# NaNd_synth_v0_1.net
KiCad netlist of a schematic drawn in EAGLE
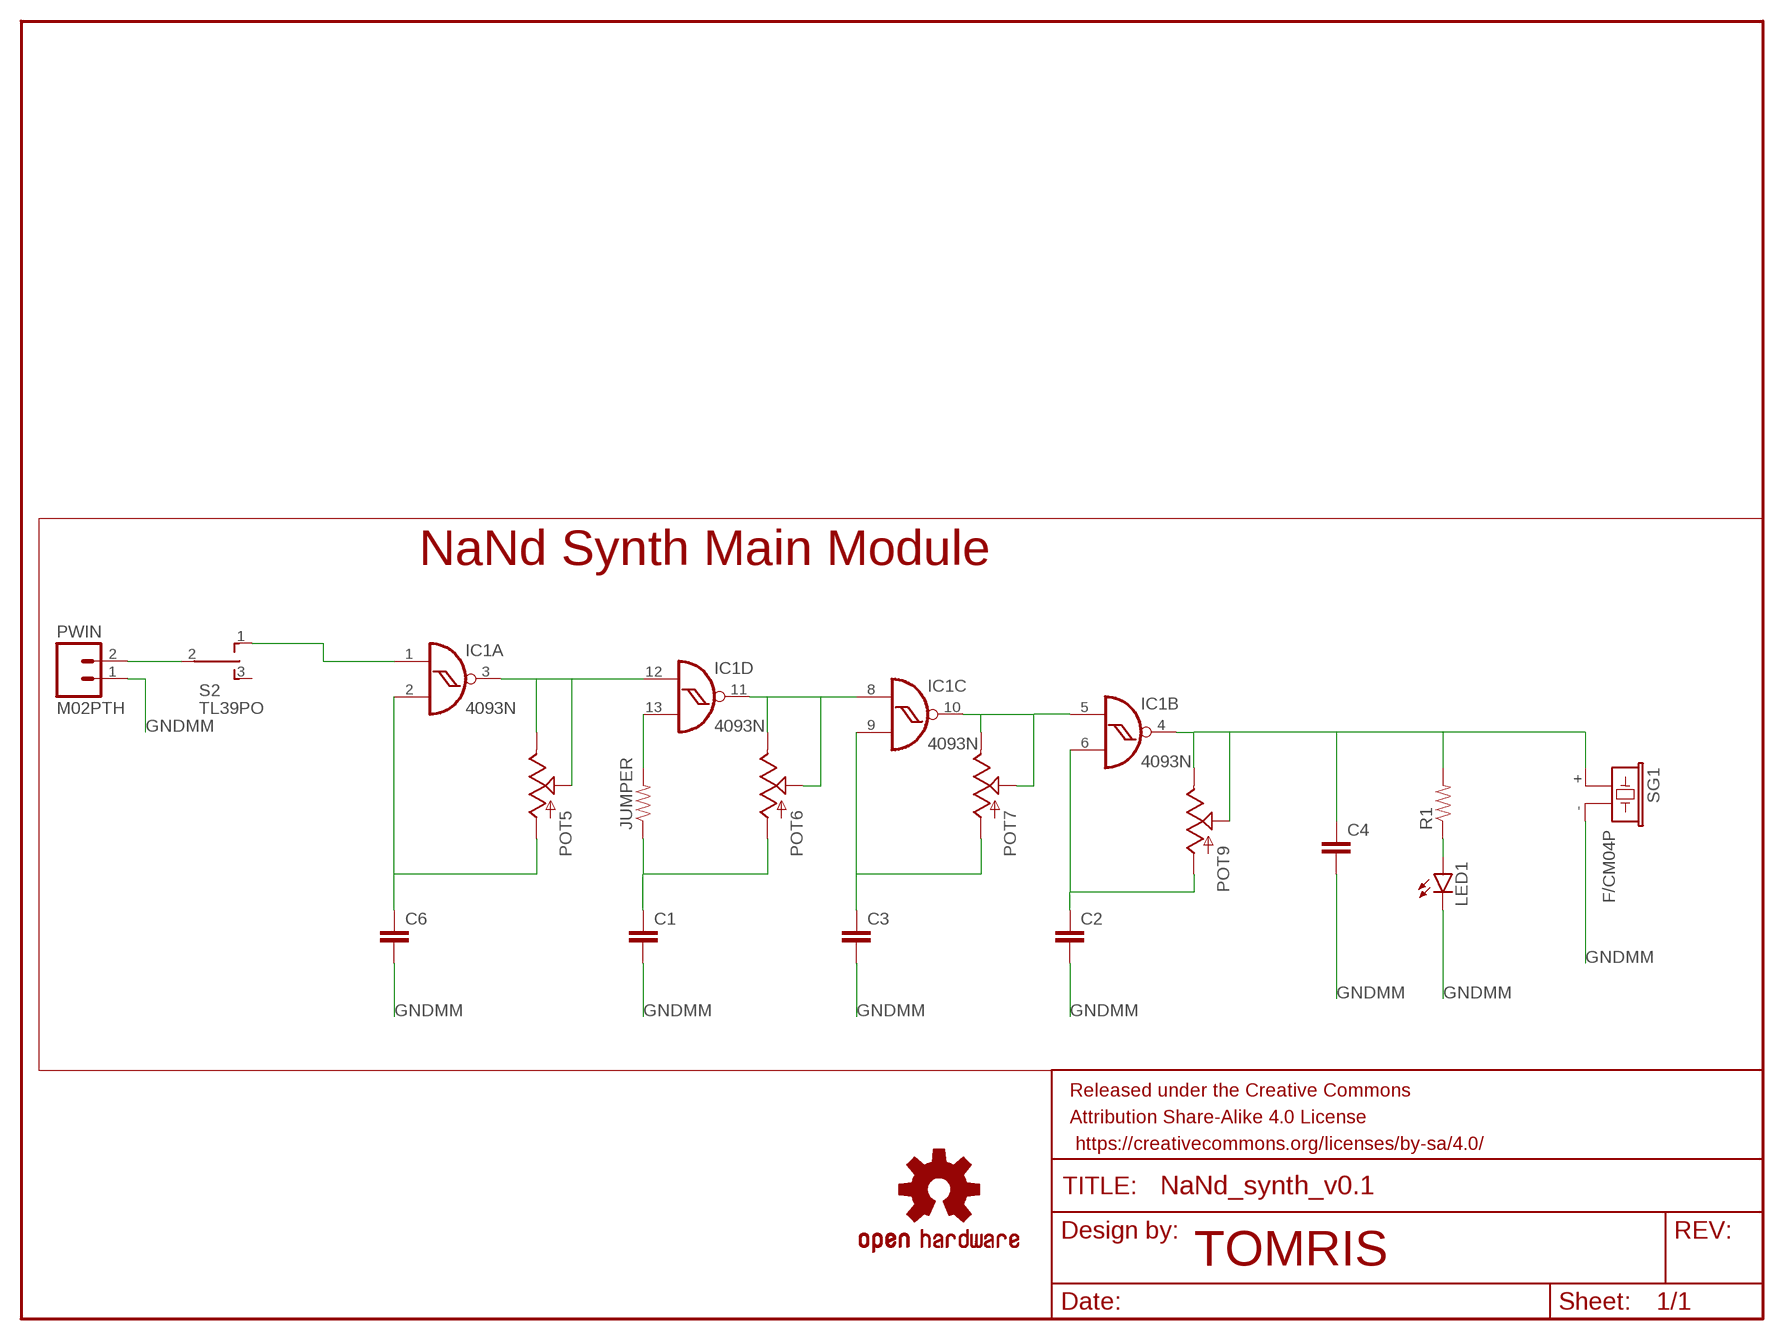
[diagram p0: schematic, sheet 1]

(export (version "E")
  (design (tool "Eeschema 10.0.6"))
  (components
    (comp (ref "C1")
      (value "CAPPTH1")
      (footprint "eagle-import:CAP-PTH-5MM")
      (libsource (lib "eagle-import") (part "CAPPTH1"))
    )
    (comp (ref "C2")
      (value "CAPPTH1")
      (footprint "eagle-import:CAP-PTH-5MM")
      (libsource (lib "eagle-import") (part "CAPPTH1"))
    )
    (comp (ref "C3")
      (value "CAPPTH1")
      (footprint "eagle-import:CAP-PTH-5MM")
      (libsource (lib "eagle-import") (part "CAPPTH1"))
    )
    (comp (ref "C4")
      (value "CAPPTH1")
      (footprint "eagle-import:CAP-PTH-5MM")
      (libsource (lib "eagle-import") (part "CAPPTH1"))
    )
    (comp (ref "C6")
      (value "CAPPTH1")
      (footprint "eagle-import:CAP-PTH-5MM")
      (libsource (lib "eagle-import") (part "CAPPTH1"))
    )
    (comp (ref "FRAME1")
      (value "FRAME-LETTER")
      (footprint "eagle-import:CREATIVE_COMMONS")
      (libsource (lib "eagle-import") (part "FRAME-LETTER"))
    )
    (comp (ref "IC1")
      (value "4093N")
      (footprint "eagle-import:DIL14")
      (libsource (lib "eagle-import") (part "4093N"))
    )
    (comp (ref "JUMPER")
      (value "RESISTORAXIAL-0.3")
      (footprint "eagle-import:AXIAL-0.3")
      (libsource (lib "eagle-import") (part "RESISTORAXIAL-0.3"))
    )
    (comp (ref "LED1")
      (value "LED-3MM-NO_SILK")
      (footprint "eagle-import:LED3MM-NS")
      (libsource (lib "eagle-import") (part "LED-3MM-NO_SILK"))
    )
    (comp (ref "LOGO1")
      (value "OSHW-LOGOM")
      (footprint "eagle-import:OSHW-LOGO-M")
      (libsource (lib "eagle-import") (part "OSHW-LOGOM"))
    )
    (comp (ref "POT5")
      (value "POTMAM")
      (footprint "eagle-import:POT_MAMMOTH")
      (libsource (lib "eagle-import") (part "POTMAM"))
    )
    (comp (ref "POT6")
      (value "POTMAM")
      (footprint "eagle-import:POT_MAMMOTH")
      (libsource (lib "eagle-import") (part "POTMAM"))
    )
    (comp (ref "POT7")
      (value "POTMAM")
      (footprint "eagle-import:POT_MAMMOTH")
      (libsource (lib "eagle-import") (part "POTMAM"))
    )
    (comp (ref "POT9")
      (value "POTMAM")
      (footprint "eagle-import:POT_MAMMOTH")
      (libsource (lib "eagle-import") (part "POTMAM"))
    )
    (comp (ref "PWIN")
      (value "M02PTH")
      (footprint "eagle-import:1X02")
      (libsource (lib "eagle-import") (part "M02PTH"))
    )
    (comp (ref "R1")
      (value "RESISTORAXIAL-0.3")
      (footprint "eagle-import:AXIAL-0.3")
      (libsource (lib "eagle-import") (part "RESISTORAXIAL-0.3"))
    )
    (comp (ref "S2")
      (value "TL39PO")
      (footprint "eagle-import:TL3XPO")
      (libsource (lib "eagle-import") (part "TL39PO"))
    )
    (comp (ref "SG1")
      (value "F/CM04P")
      (footprint "eagle-import:F_CM04P")
      (libsource (lib "eagle-import") (part "F/CM04P"))
    )
  )
  (nets
    (net (code "1") (name "/GNDMM") (class "Default")
      (node (ref "C1") (pin "2") (pinfunction "2_2") (pintype "passive"))
      (node (ref "C2") (pin "2") (pinfunction "2_2") (pintype "passive"))
      (node (ref "C3") (pin "2") (pinfunction "2_2") (pintype "passive"))
      (node (ref "C4") (pin "2") (pinfunction "2_2") (pintype "passive"))
      (node (ref "C6") (pin "2") (pinfunction "2_2") (pintype "passive"))
      (node (ref "LED1") (pin "K") (pinfunction "C_K") (pintype "passive"))
      (node (ref "PWIN") (pin "1") (pinfunction "1_1") (pintype "passive"))
      (node (ref "SG1") (pin "-") (pinfunction "2_-") (pintype "passive"))
    )
    (net (code "2") (name "Net-(IC1A-I0)") (class "Default")
      (node (ref "IC1") (pin "1") (pinfunction "I0_1") (pintype "input"))
      (node (ref "S2") (pin "1") (pinfunction "O_1") (pintype "passive"))
    )
    (net (code "3") (name "Net-(IC1A-I1)") (class "Default")
      (node (ref "C6") (pin "1") (pinfunction "1_1") (pintype "passive"))
      (node (ref "IC1") (pin "2") (pinfunction "I1_2") (pintype "input"))
      (node (ref "POT5") (pin "P$2") (pinfunction "A_P$2") (pintype "passive"))
    )
    (net (code "4") (name "Net-(IC1A-O)") (class "Default")
      (node (ref "IC1") (pin "12") (pinfunction "I0_12") (pintype "input"))
      (node (ref "IC1") (pin "3") (pinfunction "O_3") (pintype "output"))
      (node (ref "POT5") (pin "P$1") (pinfunction "S_P$1") (pintype "passive"))
      (node (ref "POT5") (pin "P$3") (pinfunction "E_P$3") (pintype "passive"))
    )
    (net (code "5") (name "Net-(IC1B-I0)") (class "Default")
      (node (ref "IC1") (pin "10") (pinfunction "O_10") (pintype "output"))
      (node (ref "IC1") (pin "5") (pinfunction "I0_5") (pintype "input"))
      (node (ref "POT7") (pin "P$1") (pinfunction "S_P$1") (pintype "passive"))
      (node (ref "POT7") (pin "P$3") (pinfunction "E_P$3") (pintype "passive"))
    )
    (net (code "6") (name "Net-(IC1B-I1)") (class "Default")
      (node (ref "C2") (pin "1") (pinfunction "1_1") (pintype "passive"))
      (node (ref "IC1") (pin "6") (pinfunction "I1_6") (pintype "input"))
      (node (ref "POT9") (pin "P$2") (pinfunction "A_P$2") (pintype "passive"))
    )
    (net (code "7") (name "Net-(IC1B-O)") (class "Default")
      (node (ref "C4") (pin "1") (pinfunction "1_1") (pintype "passive"))
      (node (ref "IC1") (pin "4") (pinfunction "O_4") (pintype "output"))
      (node (ref "POT9") (pin "P$1") (pinfunction "S_P$1") (pintype "passive"))
      (node (ref "POT9") (pin "P$3") (pinfunction "E_P$3") (pintype "passive"))
      (node (ref "R1") (pin "P$2") (pinfunction "2_P$2") (pintype "passive"))
      (node (ref "SG1") (pin "+") (pinfunction "1_+") (pintype "passive"))
    )
    (net (code "8") (name "Net-(IC1C-I0)") (class "Default")
      (node (ref "IC1") (pin "11") (pinfunction "O_11") (pintype "output"))
      (node (ref "IC1") (pin "8") (pinfunction "I0_8") (pintype "input"))
      (node (ref "POT6") (pin "P$1") (pinfunction "S_P$1") (pintype "passive"))
      (node (ref "POT6") (pin "P$3") (pinfunction "E_P$3") (pintype "passive"))
    )
    (net (code "9") (name "Net-(IC1C-I1)") (class "Default")
      (node (ref "C3") (pin "1") (pinfunction "1_1") (pintype "passive"))
      (node (ref "IC1") (pin "9") (pinfunction "I1_9") (pintype "input"))
      (node (ref "POT7") (pin "P$2") (pinfunction "A_P$2") (pintype "passive"))
    )
    (net (code "10") (name "Net-(IC1D-I1)") (class "Default")
      (node (ref "IC1") (pin "13") (pinfunction "I1_13") (pintype "input"))
      (node (ref "JUMPER") (pin "P$2") (pinfunction "2_P$2") (pintype "passive"))
    )
    (net (code "11") (name "Net-(JUMPER-1)") (class "Default")
      (node (ref "C1") (pin "1") (pinfunction "1_1") (pintype "passive"))
      (node (ref "JUMPER") (pin "P$1") (pinfunction "1_P$1") (pintype "passive"))
      (node (ref "POT6") (pin "P$2") (pinfunction "A_P$2") (pintype "passive"))
    )
    (net (code "12") (name "Net-(R1-1)") (class "Default")
      (node (ref "LED1") (pin "A") (pinfunction "A_A") (pintype "passive"))
      (node (ref "R1") (pin "P$1") (pinfunction "1_P$1") (pintype "passive"))
    )
    (net (code "13") (name "Net-(S2-P)") (class "Default")
      (node (ref "PWIN") (pin "2") (pinfunction "2_2") (pintype "passive"))
      (node (ref "S2") (pin "2") (pinfunction "P_2") (pintype "passive"))
    )
    (net (code "14") (name "unconnected-(S2-S-Pad3)") (class "Default")
      (node (ref "S2") (pin "3") (pinfunction "S_3") (pintype "passive"))
    )
  )
)
